# CT_Amp.net
KiCad netlist of a schematic drawn in EAGLE
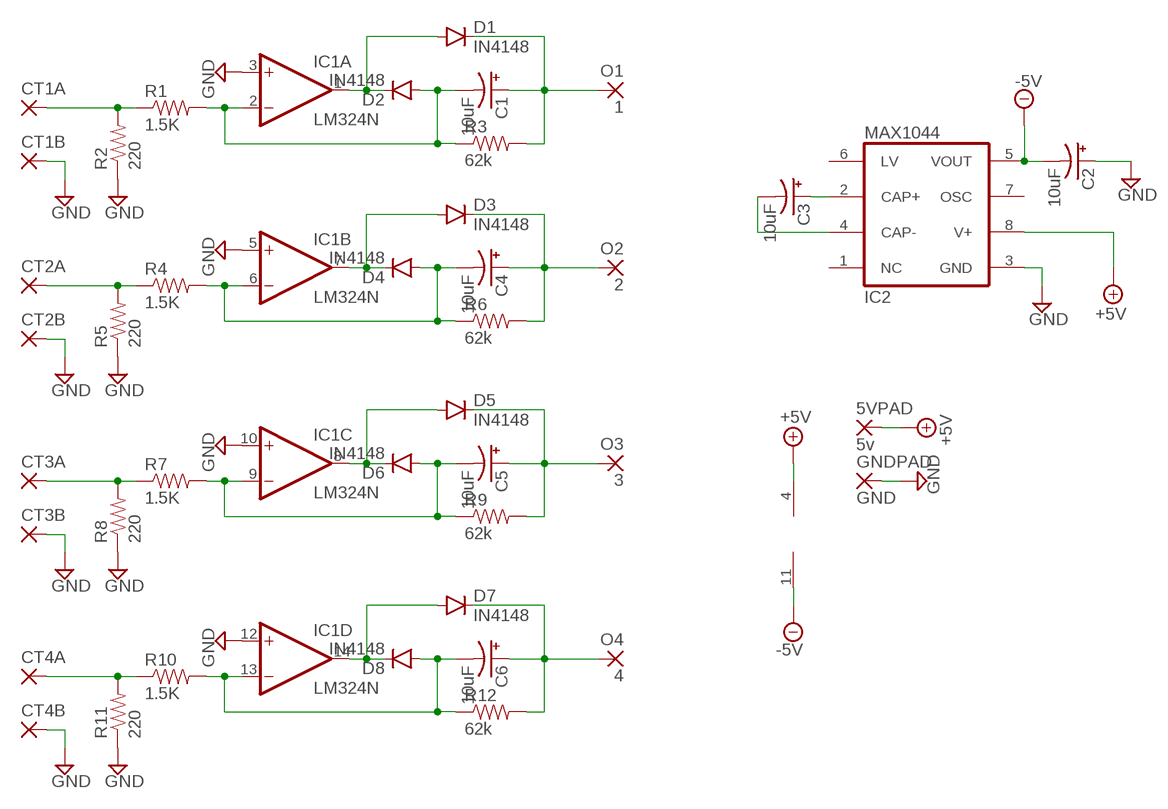
[diagram p0: schematic, sheet 1]

(export (version "E")
  (design (tool "Eeschema 10.0.6"))
  (components
    (comp (ref "5VPAD")
      (value "5v")
      (footprint "eagle-import:2,54_1,0")
      (libsource (lib "eagle-import") (part "2,54/1,0"))
    )
    (comp (ref "C1")
      (value "10uF")
      (footprint "eagle-import:E2,5-6")
      (libsource (lib "eagle-import") (part "CPOL-USE2.5-6"))
    )
    (comp (ref "C2")
      (value "10uF")
      (footprint "eagle-import:E2,5-6")
      (libsource (lib "eagle-import") (part "CPOL-USE2.5-6"))
    )
    (comp (ref "C3")
      (value "10uF")
      (footprint "eagle-import:E2,5-6")
      (libsource (lib "eagle-import") (part "CPOL-USE2.5-6"))
    )
    (comp (ref "C4")
      (value "10uF")
      (footprint "eagle-import:E2,5-6")
      (libsource (lib "eagle-import") (part "CPOL-USE2.5-6"))
    )
    (comp (ref "C5")
      (value "10uF")
      (footprint "eagle-import:E2,5-6")
      (libsource (lib "eagle-import") (part "CPOL-USE2.5-6"))
    )
    (comp (ref "C6")
      (value "10uF")
      (footprint "eagle-import:E2,5-6")
      (libsource (lib "eagle-import") (part "CPOL-USE2.5-6"))
    )
    (comp (ref "CT1A")
      (value "2,54/1,0")
      (footprint "eagle-import:2,54_1,0")
      (libsource (lib "eagle-import") (part "2,54/1,0"))
    )
    (comp (ref "CT1B")
      (value "2,54/1,0")
      (footprint "eagle-import:2,54_1,0")
      (libsource (lib "eagle-import") (part "2,54/1,0"))
    )
    (comp (ref "CT2A")
      (value "2,54/1,0")
      (footprint "eagle-import:2,54_1,0")
      (libsource (lib "eagle-import") (part "2,54/1,0"))
    )
    (comp (ref "CT2B")
      (value "2,54/1,0")
      (footprint "eagle-import:2,54_1,0")
      (libsource (lib "eagle-import") (part "2,54/1,0"))
    )
    (comp (ref "CT3A")
      (value "2,54/1,0")
      (footprint "eagle-import:2,54_1,0")
      (libsource (lib "eagle-import") (part "2,54/1,0"))
    )
    (comp (ref "CT3B")
      (value "2,54/1,0")
      (footprint "eagle-import:2,54_1,0")
      (libsource (lib "eagle-import") (part "2,54/1,0"))
    )
    (comp (ref "CT4A")
      (value "2,54/1,0")
      (footprint "eagle-import:2,54_1,0")
      (libsource (lib "eagle-import") (part "2,54/1,0"))
    )
    (comp (ref "CT4B")
      (value "2,54/1,0")
      (footprint "eagle-import:2,54_1,0")
      (libsource (lib "eagle-import") (part "2,54/1,0"))
    )
    (comp (ref "D1")
      (value "IN4148")
      (footprint "eagle-import:DIODE-1N4001")
      (libsource (lib "eagle-import") (part "DIODEPTH"))
    )
    (comp (ref "D2")
      (value "IN4148")
      (footprint "eagle-import:DIODE-1N4001")
      (libsource (lib "eagle-import") (part "DIODEPTH"))
    )
    (comp (ref "D3")
      (value "IN4148")
      (footprint "eagle-import:DIODE-1N4001")
      (libsource (lib "eagle-import") (part "DIODEPTH"))
    )
    (comp (ref "D4")
      (value "IN4148")
      (footprint "eagle-import:DIODE-1N4001")
      (libsource (lib "eagle-import") (part "DIODEPTH"))
    )
    (comp (ref "D5")
      (value "IN4148")
      (footprint "eagle-import:DIODE-1N4001")
      (libsource (lib "eagle-import") (part "DIODEPTH"))
    )
    (comp (ref "D6")
      (value "IN4148")
      (footprint "eagle-import:DIODE-1N4001")
      (libsource (lib "eagle-import") (part "DIODEPTH"))
    )
    (comp (ref "D7")
      (value "IN4148")
      (footprint "eagle-import:DIODE-1N4001")
      (libsource (lib "eagle-import") (part "DIODEPTH"))
    )
    (comp (ref "D8")
      (value "IN4148")
      (footprint "eagle-import:DIODE-1N4001")
      (libsource (lib "eagle-import") (part "DIODEPTH"))
    )
    (comp (ref "GNDPAD")
      (value "GND")
      (footprint "eagle-import:2,54_1,0")
      (libsource (lib "eagle-import") (part "2,54/1,0"))
    )
    (comp (ref "IC1")
      (value "LM324N")
      (footprint "eagle-import:DIL14")
      (libsource (lib "eagle-import") (part "LM324N"))
    )
    (comp (ref "MAX1044")
      (value "IC2")
      (footprint "eagle-import:DIL08")
      (fields (field (name "MF") "INTERSIL") (field (name "MPN") "ICL7660CPA"))
      (libsource (lib "eagle-import") (part "ICL7660CPA"))
    )
    (comp (ref "O1")
      (value "1")
      (footprint "eagle-import:2,54_1,0")
      (libsource (lib "eagle-import") (part "2,54/1,0"))
    )
    (comp (ref "O2")
      (value "2")
      (footprint "eagle-import:2,54_1,0")
      (libsource (lib "eagle-import") (part "2,54/1,0"))
    )
    (comp (ref "O3")
      (value "3")
      (footprint "eagle-import:2,54_1,0")
      (libsource (lib "eagle-import") (part "2,54/1,0"))
    )
    (comp (ref "O4")
      (value "4")
      (footprint "eagle-import:2,54_1,0")
      (libsource (lib "eagle-import") (part "2,54/1,0"))
    )
    (comp (ref "R1")
      (value "1.5K")
      (footprint "eagle-import:AXIAL-0.4")
      (libsource (lib "eagle-import") (part "RESISTORPTH-1/4W"))
    )
    (comp (ref "R2")
      (value "220")
      (footprint "eagle-import:AXIAL-0.4")
      (libsource (lib "eagle-import") (part "RESISTORPTH-1/4W"))
    )
    (comp (ref "R3")
      (value "62k")
      (footprint "eagle-import:AXIAL-0.4")
      (libsource (lib "eagle-import") (part "RESISTORPTH-1/4W"))
    )
    (comp (ref "R4")
      (value "1.5K")
      (footprint "eagle-import:AXIAL-0.4")
      (libsource (lib "eagle-import") (part "RESISTORPTH-1/4W"))
    )
    (comp (ref "R5")
      (value "220")
      (footprint "eagle-import:AXIAL-0.4")
      (libsource (lib "eagle-import") (part "RESISTORPTH-1/4W"))
    )
    (comp (ref "R6")
      (value "62k")
      (footprint "eagle-import:AXIAL-0.4")
      (libsource (lib "eagle-import") (part "RESISTORPTH-1/4W"))
    )
    (comp (ref "R7")
      (value "1.5K")
      (footprint "eagle-import:AXIAL-0.4")
      (libsource (lib "eagle-import") (part "RESISTORPTH-1/4W"))
    )
    (comp (ref "R8")
      (value "220")
      (footprint "eagle-import:AXIAL-0.4")
      (libsource (lib "eagle-import") (part "RESISTORPTH-1/4W"))
    )
    (comp (ref "R9")
      (value "62k")
      (footprint "eagle-import:AXIAL-0.4")
      (libsource (lib "eagle-import") (part "RESISTORPTH-1/4W"))
    )
    (comp (ref "R10")
      (value "1.5K")
      (footprint "eagle-import:AXIAL-0.4")
      (libsource (lib "eagle-import") (part "RESISTORPTH-1/4W"))
    )
    (comp (ref "R11")
      (value "220")
      (footprint "eagle-import:AXIAL-0.4")
      (libsource (lib "eagle-import") (part "RESISTORPTH-1/4W"))
    )
    (comp (ref "R12")
      (value "62k")
      (footprint "eagle-import:AXIAL-0.4")
      (libsource (lib "eagle-import") (part "RESISTORPTH-1/4W"))
    )
  )
  (nets
    (net (code "1") (name "+5V") (class "Default")
      (node (ref "5VPAD") (pin "1") (pinfunction "P_1") (pintype "passive"))
      (node (ref "IC1") (pin "4") (pinfunction "V+_4") (pintype "power_in"))
      (node (ref "MAX1044") (pin "8") (pinfunction "V+_8") (pintype "power_in"))
    )
    (net (code "2") (name "-5V") (class "Default")
      (node (ref "C2") (pin "-") (pinfunction "-_-") (pintype "passive"))
      (node (ref "IC1") (pin "11") (pinfunction "V-_11") (pintype "power_in"))
      (node (ref "MAX1044") (pin "5") (pinfunction "VOUT_5") (pintype "output"))
    )
    (net (code "3") (name "GND") (class "Default")
      (node (ref "C2") (pin "+") (pinfunction "+_+") (pintype "passive"))
      (node (ref "CT1B") (pin "1") (pinfunction "P_1") (pintype "passive"))
      (node (ref "CT2B") (pin "1") (pinfunction "P_1") (pintype "passive"))
      (node (ref "CT3B") (pin "1") (pinfunction "P_1") (pintype "passive"))
      (node (ref "CT4B") (pin "1") (pinfunction "P_1") (pintype "passive"))
      (node (ref "GNDPAD") (pin "1") (pinfunction "P_1") (pintype "passive"))
      (node (ref "IC1") (pin "10") (pinfunction "+IN_10") (pintype "input"))
      (node (ref "IC1") (pin "12") (pinfunction "+IN_12") (pintype "input"))
      (node (ref "IC1") (pin "3") (pinfunction "+IN_3") (pintype "input"))
      (node (ref "IC1") (pin "5") (pinfunction "+IN_5") (pintype "input"))
      (node (ref "MAX1044") (pin "3") (pinfunction "GND_3") (pintype "power_in"))
      (node (ref "R11") (pin "P$1") (pinfunction "1_P$1") (pintype "passive"))
      (node (ref "R2") (pin "P$1") (pinfunction "1_P$1") (pintype "passive"))
      (node (ref "R5") (pin "P$1") (pinfunction "1_P$1") (pintype "passive"))
      (node (ref "R8") (pin "P$1") (pinfunction "1_P$1") (pintype "passive"))
    )
    (net (code "4") (name "Net-(CT1A-P)") (class "Default")
      (node (ref "CT1A") (pin "1") (pinfunction "P_1") (pintype "passive"))
      (node (ref "R1") (pin "P$1") (pinfunction "1_P$1") (pintype "passive"))
      (node (ref "R2") (pin "P$2") (pinfunction "2_P$2") (pintype "passive"))
    )
    (net (code "5") (name "Net-(CT2A-P)") (class "Default")
      (node (ref "CT2A") (pin "1") (pinfunction "P_1") (pintype "passive"))
      (node (ref "R4") (pin "P$1") (pinfunction "1_P$1") (pintype "passive"))
      (node (ref "R5") (pin "P$2") (pinfunction "2_P$2") (pintype "passive"))
    )
    (net (code "6") (name "Net-(CT3A-P)") (class "Default")
      (node (ref "CT3A") (pin "1") (pinfunction "P_1") (pintype "passive"))
      (node (ref "R7") (pin "P$1") (pinfunction "1_P$1") (pintype "passive"))
      (node (ref "R8") (pin "P$2") (pinfunction "2_P$2") (pintype "passive"))
    )
    (net (code "7") (name "Net-(CT4A-P)") (class "Default")
      (node (ref "CT4A") (pin "1") (pinfunction "P_1") (pintype "passive"))
      (node (ref "R10") (pin "P$1") (pinfunction "1_P$1") (pintype "passive"))
      (node (ref "R11") (pin "P$2") (pinfunction "2_P$2") (pintype "passive"))
    )
    (net (code "8") (name "Net-(IC1A--IN)") (class "Default")
      (node (ref "C1") (pin "-") (pinfunction "-_-") (pintype "passive"))
      (node (ref "D2") (pin "A") (pinfunction "A_A") (pintype "passive"))
      (node (ref "IC1") (pin "2") (pinfunction "-IN_2") (pintype "input"))
      (node (ref "R1") (pin "P$2") (pinfunction "2_P$2") (pintype "passive"))
      (node (ref "R3") (pin "P$1") (pinfunction "1_P$1") (pintype "passive"))
    )
    (net (code "9") (name "Net-(IC1A-OUT)") (class "Default")
      (node (ref "D1") (pin "A") (pinfunction "A_A") (pintype "passive"))
      (node (ref "D2") (pin "C") (pinfunction "C_C") (pintype "passive"))
      (node (ref "IC1") (pin "1") (pinfunction "OUT_1") (pintype "output"))
    )
    (net (code "10") (name "Net-(IC1B--IN)") (class "Default")
      (node (ref "C4") (pin "-") (pinfunction "-_-") (pintype "passive"))
      (node (ref "D4") (pin "A") (pinfunction "A_A") (pintype "passive"))
      (node (ref "IC1") (pin "6") (pinfunction "-IN_6") (pintype "input"))
      (node (ref "R4") (pin "P$2") (pinfunction "2_P$2") (pintype "passive"))
      (node (ref "R6") (pin "P$1") (pinfunction "1_P$1") (pintype "passive"))
    )
    (net (code "11") (name "Net-(IC1B-OUT)") (class "Default")
      (node (ref "D3") (pin "A") (pinfunction "A_A") (pintype "passive"))
      (node (ref "D4") (pin "C") (pinfunction "C_C") (pintype "passive"))
      (node (ref "IC1") (pin "7") (pinfunction "OUT_7") (pintype "output"))
    )
    (net (code "12") (name "Net-(IC1C--IN)") (class "Default")
      (node (ref "C5") (pin "-") (pinfunction "-_-") (pintype "passive"))
      (node (ref "D6") (pin "A") (pinfunction "A_A") (pintype "passive"))
      (node (ref "IC1") (pin "9") (pinfunction "-IN_9") (pintype "input"))
      (node (ref "R7") (pin "P$2") (pinfunction "2_P$2") (pintype "passive"))
      (node (ref "R9") (pin "P$1") (pinfunction "1_P$1") (pintype "passive"))
    )
    (net (code "13") (name "Net-(IC1C-OUT)") (class "Default")
      (node (ref "D5") (pin "A") (pinfunction "A_A") (pintype "passive"))
      (node (ref "D6") (pin "C") (pinfunction "C_C") (pintype "passive"))
      (node (ref "IC1") (pin "8") (pinfunction "OUT_8") (pintype "output"))
    )
    (net (code "14") (name "Net-(IC1D--IN)") (class "Default")
      (node (ref "C6") (pin "-") (pinfunction "-_-") (pintype "passive"))
      (node (ref "D8") (pin "A") (pinfunction "A_A") (pintype "passive"))
      (node (ref "IC1") (pin "13") (pinfunction "-IN_13") (pintype "input"))
      (node (ref "R10") (pin "P$2") (pinfunction "2_P$2") (pintype "passive"))
      (node (ref "R12") (pin "P$1") (pinfunction "1_P$1") (pintype "passive"))
    )
    (net (code "15") (name "Net-(IC1D-OUT)") (class "Default")
      (node (ref "D7") (pin "A") (pinfunction "A_A") (pintype "passive"))
      (node (ref "D8") (pin "C") (pinfunction "C_C") (pintype "passive"))
      (node (ref "IC1") (pin "14") (pinfunction "OUT_14") (pintype "output"))
    )
    (net (code "16") (name "Net-(MAX1044-CAP+)") (class "Default")
      (node (ref "C3") (pin "+") (pinfunction "+_+") (pintype "passive"))
      (node (ref "MAX1044") (pin "2") (pinfunction "CAP+_2") (pintype "passive"))
    )
    (net (code "17") (name "Net-(MAX1044-CAP-)") (class "Default")
      (node (ref "C3") (pin "-") (pinfunction "-_-") (pintype "passive"))
      (node (ref "MAX1044") (pin "4") (pinfunction "CAP-_4") (pintype "passive"))
    )
    (net (code "18") (name "Net-(O1-P)") (class "Default")
      (node (ref "C1") (pin "+") (pinfunction "+_+") (pintype "passive"))
      (node (ref "D1") (pin "C") (pinfunction "C_C") (pintype "passive"))
      (node (ref "O1") (pin "1") (pinfunction "P_1") (pintype "passive"))
      (node (ref "R3") (pin "P$2") (pinfunction "2_P$2") (pintype "passive"))
    )
    (net (code "19") (name "Net-(O2-P)") (class "Default")
      (node (ref "C4") (pin "+") (pinfunction "+_+") (pintype "passive"))
      (node (ref "D3") (pin "C") (pinfunction "C_C") (pintype "passive"))
      (node (ref "O2") (pin "1") (pinfunction "P_1") (pintype "passive"))
      (node (ref "R6") (pin "P$2") (pinfunction "2_P$2") (pintype "passive"))
    )
    (net (code "20") (name "Net-(O3-P)") (class "Default")
      (node (ref "C5") (pin "+") (pinfunction "+_+") (pintype "passive"))
      (node (ref "D5") (pin "C") (pinfunction "C_C") (pintype "passive"))
      (node (ref "O3") (pin "1") (pinfunction "P_1") (pintype "passive"))
      (node (ref "R9") (pin "P$2") (pinfunction "2_P$2") (pintype "passive"))
    )
    (net (code "21") (name "Net-(O4-P)") (class "Default")
      (node (ref "C6") (pin "+") (pinfunction "+_+") (pintype "passive"))
      (node (ref "D7") (pin "C") (pinfunction "C_C") (pintype "passive"))
      (node (ref "O4") (pin "1") (pinfunction "P_1") (pintype "passive"))
      (node (ref "R12") (pin "P$2") (pinfunction "2_P$2") (pintype "passive"))
    )
    (net (code "22") (name "unconnected-(MAX1044-LV-Pad6)") (class "Default")
      (node (ref "MAX1044") (pin "6") (pinfunction "LV_6") (pintype "passive"))
    )
    (net (code "23") (name "unconnected-(MAX1044-NC-Pad1)") (class "Default")
      (node (ref "MAX1044") (pin "1") (pinfunction "NC_1") (pintype "no_connect"))
    )
    (net (code "24") (name "unconnected-(MAX1044-OSC-Pad7)") (class "Default")
      (node (ref "MAX1044") (pin "7") (pinfunction "OSC_7") (pintype "output"))
    )
  )
)
